# car1r1.net
KiCad netlist of a schematic drawn in EAGLE
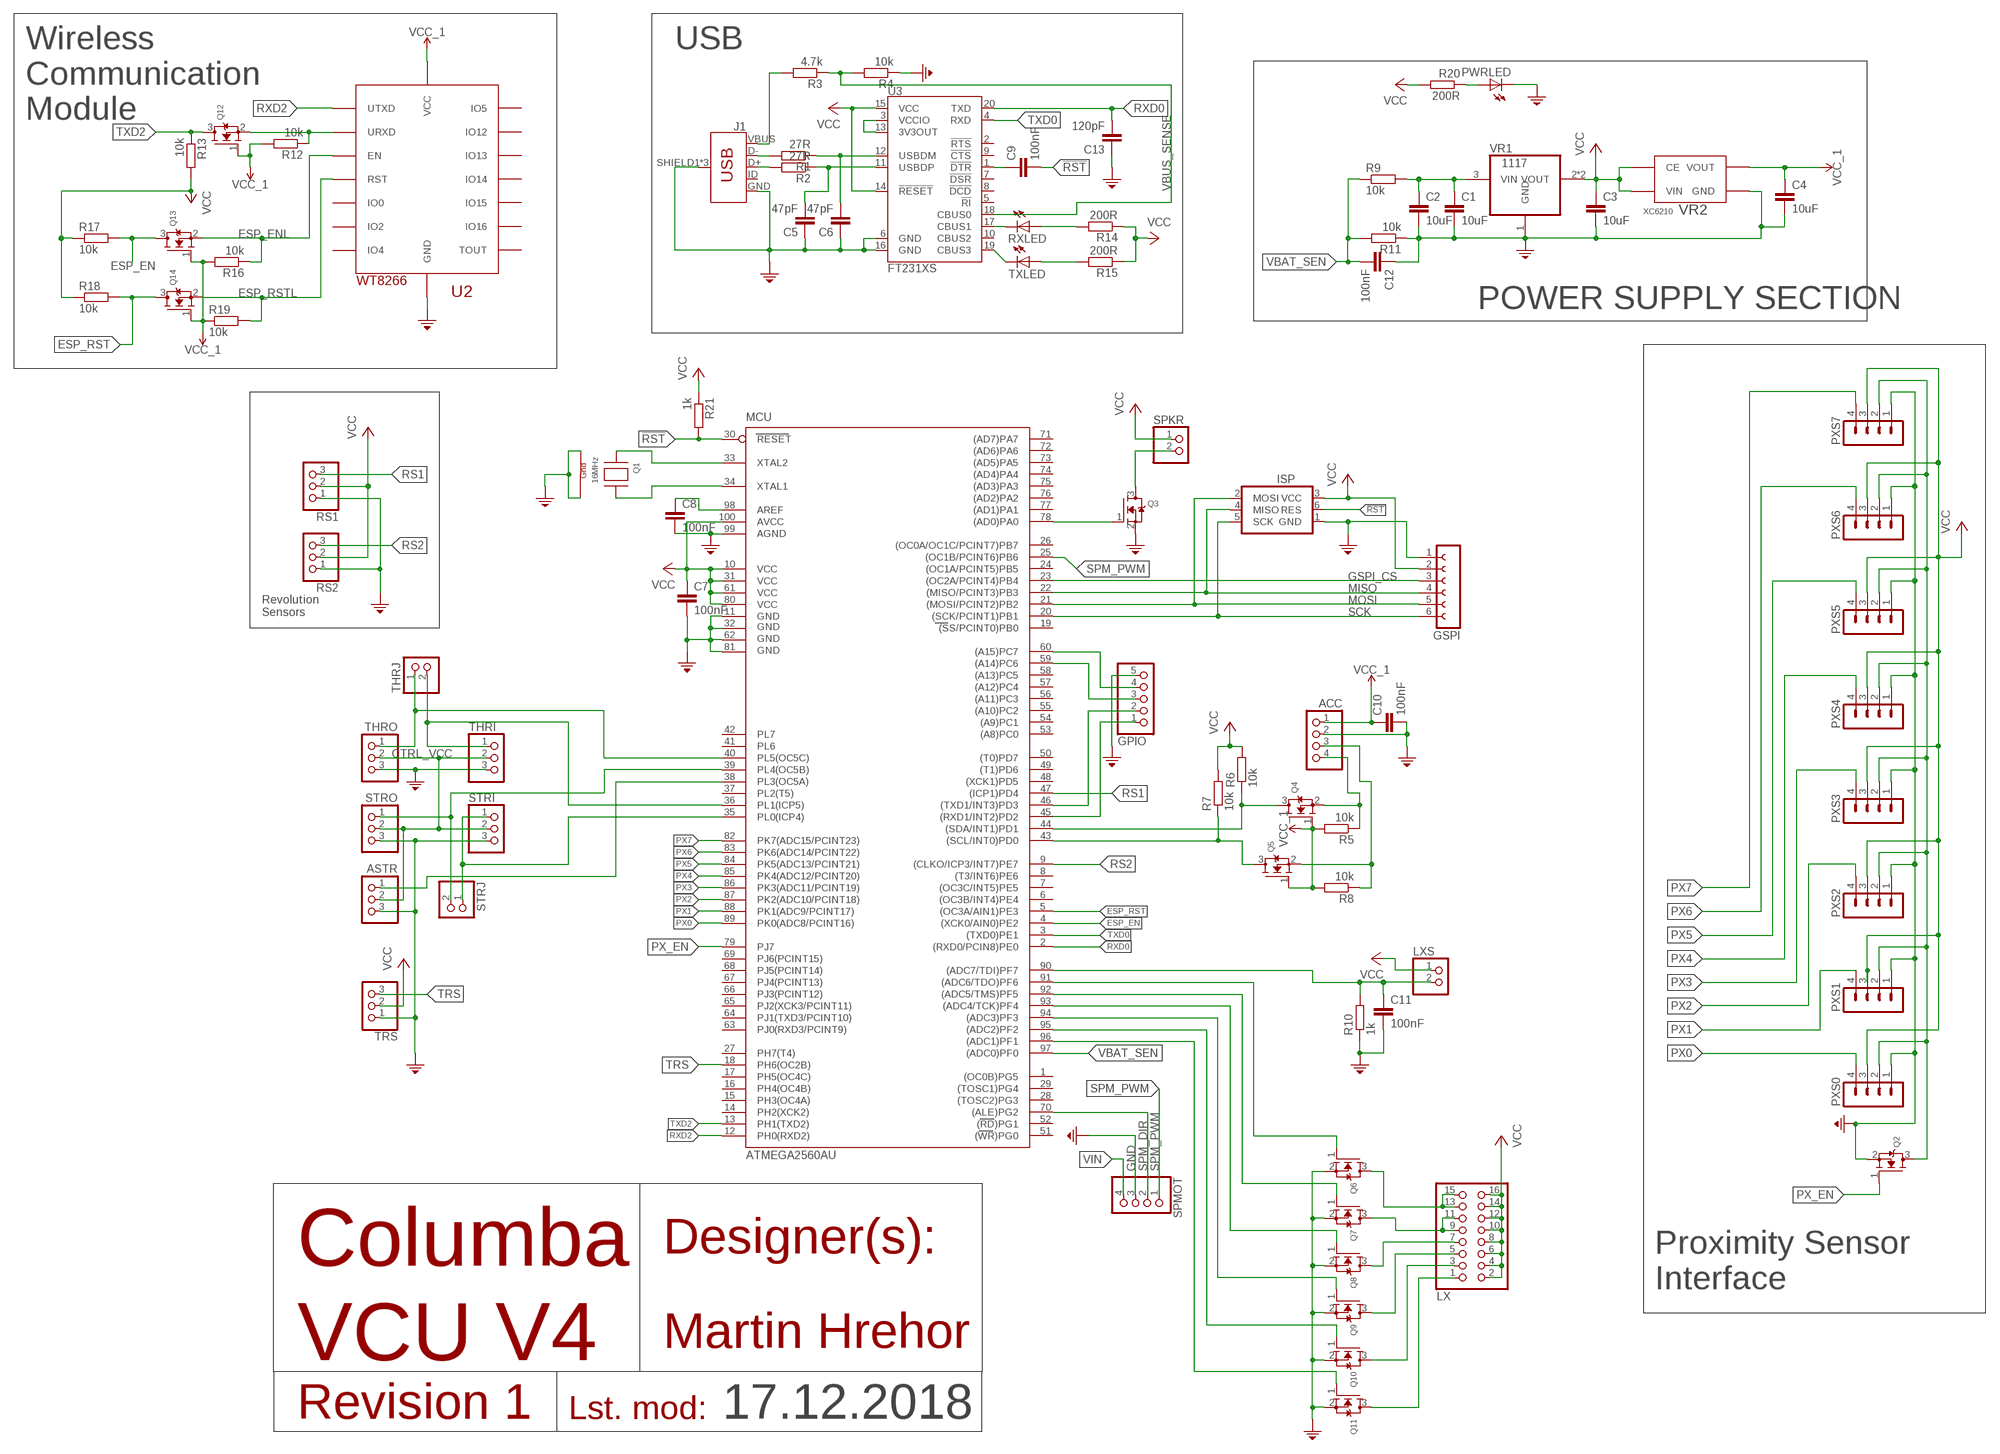
[diagram p0: schematic, sheet 1]

(export (version "E")
  (design (tool "Eeschema 10.0.6"))
  (components
    (comp (ref "ACC")
      (value "PINHD-1X4/90")
      (footprint "eagle-import:1X04_90")
      (libsource (lib "eagle-import") (part "PINHD-1X4/90"))
    )
    (comp (ref "ASTR")
      (value "PINHD-1X3")
      (footprint "eagle-import:1X03")
      (libsource (lib "eagle-import") (part "PINHD-1X3"))
    )
    (comp (ref "C1")
      (value "10uF")
      (footprint "eagle-import:C1206")
      (libsource (lib "eagle-import") (part "C-EUC1206"))
    )
    (comp (ref "C2")
      (value "10uF")
      (footprint "eagle-import:C1206")
      (libsource (lib "eagle-import") (part "C-EUC1206"))
    )
    (comp (ref "C3")
      (value "10uF")
      (footprint "eagle-import:C1206")
      (libsource (lib "eagle-import") (part "C-EUC1206"))
    )
    (comp (ref "C4")
      (value "10uF")
      (footprint "eagle-import:C1206")
      (libsource (lib "eagle-import") (part "C-EUC1206"))
    )
    (comp (ref "C5")
      (value "47pF")
      (footprint "eagle-import:C0603")
      (libsource (lib "eagle-import") (part "C-EUC0603"))
    )
    (comp (ref "C6")
      (value "47pF")
      (footprint "eagle-import:C0603")
      (libsource (lib "eagle-import") (part "C-EUC0603"))
    )
    (comp (ref "C7")
      (value "100nF")
      (footprint "eagle-import:C1206")
      (libsource (lib "eagle-import") (part "C-EUC1206"))
    )
    (comp (ref "C8")
      (value "100nF")
      (footprint "eagle-import:C1206")
      (libsource (lib "eagle-import") (part "C-EUC1206"))
    )
    (comp (ref "C9")
      (value "100nF")
      (footprint "eagle-import:C1206")
      (libsource (lib "eagle-import") (part "C-EUC1206"))
    )
    (comp (ref "C10")
      (value "100nF")
      (footprint "eagle-import:C1206")
      (libsource (lib "eagle-import") (part "C-EUC1206"))
    )
    (comp (ref "C11")
      (value "100nF")
      (footprint "eagle-import:C1206")
      (libsource (lib "eagle-import") (part "C-EUC1206"))
    )
    (comp (ref "C12")
      (value "100nF")
      (footprint "eagle-import:C1206")
      (libsource (lib "eagle-import") (part "C-EUC1206"))
    )
    (comp (ref "C13")
      (value "120pF")
      (footprint "eagle-import:C0603")
      (libsource (lib "eagle-import") (part "C-EUC0603"))
    )
    (comp (ref "GPIO")
      (value "PINHD-1X5")
      (footprint "eagle-import:1X05")
      (libsource (lib "eagle-import") (part "PINHD-1X5"))
    )
    (comp (ref "GSPI")
      (value "FE06W")
      (footprint "eagle-import:FE06W")
      (libsource (lib "eagle-import") (part "FE06W"))
    )
    (comp (ref "ISP")
      (value "ISP")
      (footprint "eagle-import:ISP")
      (libsource (lib "eagle-import") (part "ISP"))
    )
    (comp (ref "J1")
      (value "USB_MICRO-B_FEMALE-SMT")
      (footprint "eagle-import:USB-B-MICRO-SMD")
      (libsource (lib "eagle-import") (part "USB_MICRO-B_FEMALE-SMT"))
    )
    (comp (ref "LX")
      (value "PINHD-2X8")
      (footprint "eagle-import:2X08")
      (libsource (lib "eagle-import") (part "PINHD-2X8"))
    )
    (comp (ref "LXS")
      (value "PINHD-1X2")
      (footprint "eagle-import:1X02")
      (libsource (lib "eagle-import") (part "PINHD-1X2"))
    )
    (comp (ref "MCU")
      (value "ATMEGA2560AU")
      (footprint "eagle-import:TQFP100")
      (libsource (lib "eagle-import") (part "ATMEGA2560AU"))
    )
    (comp (ref "PWRLED")
      (value "LEDCHIP-LED0603")
      (footprint "eagle-import:CHIP-LED0603")
      (libsource (lib "eagle-import") (part "LEDCHIP-LED0603"))
    )
    (comp (ref "PXS0")
      (value "MA04-1")
      (footprint "eagle-import:MA04-1")
      (libsource (lib "eagle-import") (part "MA04-1"))
    )
    (comp (ref "PXS1")
      (value "MA04-1")
      (footprint "eagle-import:MA04-1")
      (libsource (lib "eagle-import") (part "MA04-1"))
    )
    (comp (ref "PXS2")
      (value "MA04-1")
      (footprint "eagle-import:MA04-1")
      (libsource (lib "eagle-import") (part "MA04-1"))
    )
    (comp (ref "PXS3")
      (value "MA04-1")
      (footprint "eagle-import:MA04-1")
      (libsource (lib "eagle-import") (part "MA04-1"))
    )
    (comp (ref "PXS4")
      (value "MA04-1")
      (footprint "eagle-import:MA04-1")
      (libsource (lib "eagle-import") (part "MA04-1"))
    )
    (comp (ref "PXS5")
      (value "MA04-1")
      (footprint "eagle-import:MA04-1")
      (libsource (lib "eagle-import") (part "MA04-1"))
    )
    (comp (ref "PXS6")
      (value "MA04-1")
      (footprint "eagle-import:MA04-1")
      (libsource (lib "eagle-import") (part "MA04-1"))
    )
    (comp (ref "PXS7")
      (value "MA04-1")
      (footprint "eagle-import:MA04-1")
      (libsource (lib "eagle-import") (part "MA04-1"))
    )
    (comp (ref "Q1")
      (value "16MHz")
      (footprint "eagle-import:NX3225")
      (libsource (lib "eagle-import") (part "XTAL-4-3225"))
    )
    (comp (ref "Q2")
      (value "MOSFET-NREFLOW")
      (footprint "eagle-import:SOT23")
      (libsource (lib "eagle-import") (part "MOSFET-NREFLOW"))
    )
    (comp (ref "Q3")
      (value "MOSFET-NREFLOW")
      (footprint "eagle-import:SOT23")
      (libsource (lib "eagle-import") (part "MOSFET-NREFLOW"))
    )
    (comp (ref "Q4")
      (value "MOSFET-NREFLOW")
      (footprint "eagle-import:SOT23")
      (libsource (lib "eagle-import") (part "MOSFET-NREFLOW"))
    )
    (comp (ref "Q5")
      (value "MOSFET-NREFLOW")
      (footprint "eagle-import:SOT23")
      (libsource (lib "eagle-import") (part "MOSFET-NREFLOW"))
    )
    (comp (ref "Q6")
      (value "MOSFET-NREFLOW")
      (footprint "eagle-import:SOT23")
      (libsource (lib "eagle-import") (part "MOSFET-NREFLOW"))
    )
    (comp (ref "Q7")
      (value "MOSFET-NREFLOW")
      (footprint "eagle-import:SOT23")
      (libsource (lib "eagle-import") (part "MOSFET-NREFLOW"))
    )
    (comp (ref "Q8")
      (value "MOSFET-NREFLOW")
      (footprint "eagle-import:SOT23")
      (libsource (lib "eagle-import") (part "MOSFET-NREFLOW"))
    )
    (comp (ref "Q9")
      (value "MOSFET-NREFLOW")
      (footprint "eagle-import:SOT23")
      (libsource (lib "eagle-import") (part "MOSFET-NREFLOW"))
    )
    (comp (ref "Q10")
      (value "MOSFET-NREFLOW")
      (footprint "eagle-import:SOT23")
      (libsource (lib "eagle-import") (part "MOSFET-NREFLOW"))
    )
    (comp (ref "Q11")
      (value "MOSFET-NREFLOW")
      (footprint "eagle-import:SOT23")
      (libsource (lib "eagle-import") (part "MOSFET-NREFLOW"))
    )
    (comp (ref "Q12")
      (value "MOSFET-NREFLOW")
      (footprint "eagle-import:SOT23")
      (libsource (lib "eagle-import") (part "MOSFET-NREFLOW"))
    )
    (comp (ref "Q13")
      (value "MOSFET-NREFLOW")
      (footprint "eagle-import:SOT23")
      (libsource (lib "eagle-import") (part "MOSFET-NREFLOW"))
    )
    (comp (ref "Q14")
      (value "MOSFET-NREFLOW")
      (footprint "eagle-import:SOT23")
      (libsource (lib "eagle-import") (part "MOSFET-NREFLOW"))
    )
    (comp (ref "R1")
      (value "27R")
      (footprint "eagle-import:R0603")
      (libsource (lib "eagle-import") (part "R-EU_R0603"))
    )
    (comp (ref "R2")
      (value "27R")
      (footprint "eagle-import:R0603")
      (libsource (lib "eagle-import") (part "R-EU_R0603"))
    )
    (comp (ref "R3")
      (value "4.7k")
      (footprint "eagle-import:R0603")
      (libsource (lib "eagle-import") (part "R-EU_R0603"))
    )
    (comp (ref "R4")
      (value "10k")
      (footprint "eagle-import:R0603")
      (libsource (lib "eagle-import") (part "R-EU_R0603"))
    )
    (comp (ref "R5")
      (value "10k")
      (footprint "eagle-import:R0603")
      (libsource (lib "eagle-import") (part "R-EU_R0603"))
    )
    (comp (ref "R6")
      (value "10k")
      (footprint "eagle-import:R0603")
      (libsource (lib "eagle-import") (part "R-EU_R0603"))
    )
    (comp (ref "R7")
      (value "10k")
      (footprint "eagle-import:R0603")
      (libsource (lib "eagle-import") (part "R-EU_R0603"))
    )
    (comp (ref "R8")
      (value "10k")
      (footprint "eagle-import:R0603")
      (libsource (lib "eagle-import") (part "R-EU_R0603"))
    )
    (comp (ref "R9")
      (value "10k")
      (footprint "eagle-import:R0805")
      (libsource (lib "eagle-import") (part "R-EU_R0805"))
    )
    (comp (ref "R10")
      (value "1k")
      (footprint "eagle-import:R0603")
      (libsource (lib "eagle-import") (part "R-EU_R0603"))
    )
    (comp (ref "R11")
      (value "10k")
      (footprint "eagle-import:R0805")
      (libsource (lib "eagle-import") (part "R-EU_R0805"))
    )
    (comp (ref "R12")
      (value "10k")
      (footprint "eagle-import:R0603")
      (libsource (lib "eagle-import") (part "R-EU_R0603"))
    )
    (comp (ref "R13")
      (value "10k")
      (footprint "eagle-import:R0603")
      (libsource (lib "eagle-import") (part "R-EU_R0603"))
    )
    (comp (ref "R14")
      (value "200R")
      (footprint "eagle-import:R0603")
      (libsource (lib "eagle-import") (part "R-EU_R0603"))
    )
    (comp (ref "R15")
      (value "200R")
      (footprint "eagle-import:R0603")
      (libsource (lib "eagle-import") (part "R-EU_R0603"))
    )
    (comp (ref "R16")
      (value "10k")
      (footprint "eagle-import:R0603")
      (libsource (lib "eagle-import") (part "R-EU_R0603"))
    )
    (comp (ref "R17")
      (value "10k")
      (footprint "eagle-import:R0603")
      (libsource (lib "eagle-import") (part "R-EU_R0603"))
    )
    (comp (ref "R18")
      (value "10k")
      (footprint "eagle-import:R0603")
      (libsource (lib "eagle-import") (part "R-EU_R0603"))
    )
    (comp (ref "R19")
      (value "10k")
      (footprint "eagle-import:R0603")
      (libsource (lib "eagle-import") (part "R-EU_R0603"))
    )
    (comp (ref "R20")
      (value "200R")
      (footprint "eagle-import:R0603")
      (libsource (lib "eagle-import") (part "R-EU_R0603"))
    )
    (comp (ref "R21")
      (value "1k")
      (footprint "eagle-import:R0603")
      (libsource (lib "eagle-import") (part "R-EU_R0603"))
    )
    (comp (ref "RS1")
      (value "PINHD-1X3")
      (footprint "eagle-import:1X03")
      (libsource (lib "eagle-import") (part "PINHD-1X3"))
    )
    (comp (ref "RS2")
      (value "PINHD-1X3")
      (footprint "eagle-import:1X03")
      (libsource (lib "eagle-import") (part "PINHD-1X3"))
    )
    (comp (ref "RXLED")
      (value "LEDCHIP-LED0603")
      (footprint "eagle-import:CHIP-LED0603")
      (libsource (lib "eagle-import") (part "LEDCHIP-LED0603"))
    )
    (comp (ref "SPKR")
      (value "PINHD-1X2")
      (footprint "eagle-import:1X02")
      (libsource (lib "eagle-import") (part "PINHD-1X2"))
    )
    (comp (ref "SPMOT")
      (value "PINHD-1X4/90")
      (footprint "eagle-import:1X04_90")
      (libsource (lib "eagle-import") (part "PINHD-1X4/90"))
    )
    (comp (ref "STRI")
      (value "PINHD-1X3")
      (footprint "eagle-import:1X03")
      (libsource (lib "eagle-import") (part "PINHD-1X3"))
    )
    (comp (ref "STRJ")
      (value "PINHD-1X2")
      (footprint "eagle-import:1X02")
      (libsource (lib "eagle-import") (part "PINHD-1X2"))
    )
    (comp (ref "STRO")
      (value "PINHD-1X3")
      (footprint "eagle-import:1X03")
      (libsource (lib "eagle-import") (part "PINHD-1X3"))
    )
    (comp (ref "THRI")
      (value "PINHD-1X3")
      (footprint "eagle-import:1X03")
      (libsource (lib "eagle-import") (part "PINHD-1X3"))
    )
    (comp (ref "THRJ")
      (value "PINHD-1X2")
      (footprint "eagle-import:1X02")
      (libsource (lib "eagle-import") (part "PINHD-1X2"))
    )
    (comp (ref "THRO")
      (value "PINHD-1X3")
      (footprint "eagle-import:1X03")
      (libsource (lib "eagle-import") (part "PINHD-1X3"))
    )
    (comp (ref "TRS")
      (value "PINHD-1X3")
      (footprint "eagle-import:1X03")
      (libsource (lib "eagle-import") (part "PINHD-1X3"))
    )
    (comp (ref "TXLED")
      (value "LEDCHIP-LED0603")
      (footprint "eagle-import:CHIP-LED0603")
      (libsource (lib "eagle-import") (part "LEDCHIP-LED0603"))
    )
    (comp (ref "U2")
      (value "WT8266")
      (footprint "eagle-import:WT8266")
      (libsource (lib "eagle-import") (part "WT8266"))
    )
    (comp (ref "U3")
      (value "FT231XS")
      (footprint "eagle-import:SSOP20_L")
      (libsource (lib "eagle-import") (part "FT231XS"))
    )
    (comp (ref "VR1")
      (value "1117")
      (footprint "eagle-import:SOT223")
      (fields (field (name "MPN") "REG1117"))
      (libsource (lib "eagle-import") (part "REG1117"))
    )
    (comp (ref "VR2")
      (value "XC6210")
      (footprint "eagle-import:SOT25")
      (libsource (lib "eagle-import") (part "XC6210"))
    )
  )
  (nets
    (net (code "1") (name "/CTRL_VCC") (class "Default")
      (node (ref "ASTR") (pin "2") (pinfunction "2_2") (pintype "passive"))
      (node (ref "STRI") (pin "2") (pinfunction "2_2") (pintype "passive"))
      (node (ref "STRO") (pin "2") (pinfunction "2_2") (pintype "passive"))
      (node (ref "THRI") (pin "2") (pinfunction "2_2") (pintype "passive"))
      (node (ref "THRO") (pin "2") (pinfunction "2_2") (pintype "passive"))
    )
    (net (code "2") (name "/ESP_ENL") (class "Default")
      (node (ref "Q13") (pin "2") (pinfunction "S_2") (pintype "bidirectional"))
      (node (ref "R16") (pin "1") (pinfunction "1_1") (pintype "passive"))
      (node (ref "U2") (pin "EN") (pinfunction "EN_EN") (pintype "bidirectional"))
    )
    (net (code "3") (name "/ESP_RSTL") (class "Default")
      (node (ref "Q14") (pin "2") (pinfunction "S_2") (pintype "bidirectional"))
      (node (ref "R19") (pin "2") (pinfunction "2_2") (pintype "passive"))
      (node (ref "U2") (pin "RST") (pinfunction "RST_RST") (pintype "bidirectional"))
    )
    (net (code "4") (name "/GSPI_CS") (class "Default")
      (node (ref "GSPI") (pin "3") (pinfunction "3_3") (pintype "passive"))
      (node (ref "MCU") (pin "23") (pinfunction "(OC2A/PCINT4)PB4_23") (pintype "bidirectional"))
    )
    (net (code "5") (name "/MISO") (class "Default")
      (node (ref "GSPI") (pin "4") (pinfunction "4_4") (pintype "passive"))
      (node (ref "ISP") (pin "4") (pinfunction "MISO_4") (pintype "bidirectional"))
      (node (ref "MCU") (pin "22") (pinfunction "(MISO/PCINT3)PB3_22") (pintype "bidirectional"))
    )
    (net (code "6") (name "/MOSI") (class "Default")
      (node (ref "GSPI") (pin "5") (pinfunction "5_5") (pintype "passive"))
      (node (ref "ISP") (pin "2") (pinfunction "MOSI_2") (pintype "bidirectional"))
      (node (ref "MCU") (pin "21") (pinfunction "(MOSI/PCINT2)PB2_21") (pintype "bidirectional"))
    )
    (net (code "7") (name "/SCK") (class "Default")
      (node (ref "GSPI") (pin "6") (pinfunction "6_6") (pintype "passive"))
      (node (ref "ISP") (pin "5") (pinfunction "SCK_5") (pintype "bidirectional"))
      (node (ref "MCU") (pin "20") (pinfunction "(SCK/PCINT1)PB1_20") (pintype "bidirectional"))
    )
    (net (code "8") (name "/SPM_DIR") (class "Default")
      (node (ref "MCU") (pin "70") (pinfunction "(ALE)PG2_70") (pintype "bidirectional"))
      (node (ref "SPMOT") (pin "2") (pinfunction "2_2") (pintype "passive"))
    )
    (net (code "9") (name "/VBUS_SENSE") (class "Default")
      (node (ref "R3") (pin "1") (pinfunction "1_1") (pintype "passive"))
      (node (ref "R4") (pin "2") (pinfunction "2_2") (pintype "passive"))
      (node (ref "U3") (pin "18") (pinfunction "CBUS0_18") (pintype "bidirectional"))
    )
    (net (code "10") (name "/~{RST}") (class "Default")
      (node (ref "C9") (pin "2") (pinfunction "2_2") (pintype "passive"))
      (node (ref "ISP") (pin "6") (pinfunction "RES_6") (pintype "bidirectional"))
      (node (ref "MCU") (pin "30") (pinfunction "RESET_30") (pintype "input"))
      (node (ref "R21") (pin "2") (pinfunction "2_2") (pintype "passive"))
    )
    (net (code "11") (name "ESP_EN") (class "Default")
      (node (ref "MCU") (pin "4") (pinfunction "(XCK0/AIN0)PE2_4") (pintype "bidirectional"))
      (node (ref "Q13") (pin "3") (pinfunction "D_3") (pintype "bidirectional"))
      (node (ref "R17") (pin "2") (pinfunction "2_2") (pintype "passive"))
    )
    (net (code "12") (name "ESP_RST") (class "Default")
      (node (ref "MCU") (pin "5") (pinfunction "(OC3A/AIN1)PE3_5") (pintype "bidirectional"))
      (node (ref "Q14") (pin "3") (pinfunction "D_3") (pintype "bidirectional"))
      (node (ref "R18") (pin "2") (pinfunction "2_2") (pintype "passive"))
    )
    (net (code "13") (name "GND") (class "Default")
      (node (ref "ACC") (pin "2") (pinfunction "2_2") (pintype "passive"))
      (node (ref "ASTR") (pin "3") (pinfunction "3_3") (pintype "passive"))
      (node (ref "C1") (pin "2") (pinfunction "2_2") (pintype "passive"))
      (node (ref "C10") (pin "2") (pinfunction "2_2") (pintype "passive"))
      (node (ref "C11") (pin "2") (pinfunction "2_2") (pintype "passive"))
      (node (ref "C12") (pin "1") (pinfunction "1_1") (pintype "passive"))
      (node (ref "C13") (pin "1") (pinfunction "1_1") (pintype "passive"))
      (node (ref "C2") (pin "2") (pinfunction "2_2") (pintype "passive"))
      (node (ref "C3") (pin "2") (pinfunction "2_2") (pintype "passive"))
      (node (ref "C4") (pin "2") (pinfunction "2_2") (pintype "passive"))
      (node (ref "C5") (pin "1") (pinfunction "1_1") (pintype "passive"))
      (node (ref "C6") (pin "1") (pinfunction "1_1") (pintype "passive"))
      (node (ref "C7") (pin "2") (pinfunction "2_2") (pintype "passive"))
      (node (ref "C8") (pin "2") (pinfunction "2_2") (pintype "passive"))
      (node (ref "GPIO") (pin "5") (pinfunction "5_5") (pintype "passive"))
      (node (ref "GSPI") (pin "1") (pinfunction "1_1") (pintype "passive"))
      (node (ref "ISP") (pin "1") (pinfunction "GND_1") (pintype "bidirectional"))
      (node (ref "J1") (pin "GND") (pinfunction "GND_GND") (pintype "power_in"))
      (node (ref "J1") (pin "SHIELD1") (pinfunction "SHIELD_SHIELD1") (pintype "bidirectional"))
      (node (ref "J1") (pin "SHIELD2") (pinfunction "SHIELD_SHIELD2") (pintype "bidirectional"))
      (node (ref "J1") (pin "SHIELD3") (pinfunction "SHIELD_SHIELD3") (pintype "bidirectional"))
      (node (ref "MCU") (pin "11") (pinfunction "GND_11") (pintype "power_in"))
      (node (ref "MCU") (pin "32") (pinfunction "GND1_32") (pintype "power_in"))
      (node (ref "MCU") (pin "62") (pinfunction "GND2_62") (pintype "power_in"))
      (node (ref "MCU") (pin "81") (pinfunction "GND3_81") (pintype "power_in"))
      (node (ref "MCU") (pin "99") (pinfunction "AGND_99") (pintype "power_in"))
      (node (ref "PWRLED") (pin "C") (pinfunction "C_C") (pintype "passive"))
      (node (ref "PXS0") (pin "1") (pinfunction "1_1") (pintype "passive"))
      (node (ref "PXS1") (pin "1") (pinfunction "1_1") (pintype "passive"))
      (node (ref "PXS2") (pin "1") (pinfunction "1_1") (pintype "passive"))
      (node (ref "PXS3") (pin "1") (pinfunction "1_1") (pintype "passive"))
      (node (ref "PXS4") (pin "1") (pinfunction "1_1") (pintype "passive"))
      (node (ref "PXS5") (pin "1") (pinfunction "1_1") (pintype "passive"))
      (node (ref "PXS6") (pin "1") (pinfunction "1_1") (pintype "passive"))
      (node (ref "PXS7") (pin "1") (pinfunction "1_1") (pintype "passive"))
      (node (ref "Q1") (pin "2") (pinfunction "G2_2") (pintype "power_in"))
      (node (ref "Q1") (pin "4") (pinfunction "G1_4") (pintype "power_in"))
      (node (ref "Q10") (pin "2") (pinfunction "S_2") (pintype "bidirectional"))
      (node (ref "Q11") (pin "2") (pinfunction "S_2") (pintype "bidirectional"))
      (node (ref "Q2") (pin "2") (pinfunction "S_2") (pintype "bidirectional"))
      (node (ref "Q3") (pin "2") (pinfunction "S_2") (pintype "bidirectional"))
      (node (ref "Q6") (pin "2") (pinfunction "S_2") (pintype "bidirectional"))
      (node (ref "Q7") (pin "2") (pinfunction "S_2") (pintype "bidirectional"))
      (node (ref "Q8") (pin "2") (pinfunction "S_2") (pintype "bidirectional"))
      (node (ref "Q9") (pin "2") (pinfunction "S_2") (pintype "bidirectional"))
      (node (ref "R10") (pin "1") (pinfunction "1_1") (pintype "passive"))
      (node (ref "R11") (pin "1") (pinfunction "1_1") (pintype "passive"))
      (node (ref "R4") (pin "1") (pinfunction "1_1") (pintype "passive"))
      (node (ref "RS1") (pin "1") (pinfunction "1_1") (pintype "passive"))
      (node (ref "RS2") (pin "1") (pinfunction "1_1") (pintype "passive"))
      (node (ref "SPMOT") (pin "3") (pinfunction "3_3") (pintype "passive"))
      (node (ref "STRI") (pin "3") (pinfunction "3_3") (pintype "passive"))
      (node (ref "STRO") (pin "3") (pinfunction "3_3") (pintype "passive"))
      (node (ref "THRI") (pin "3") (pinfunction "3_3") (pintype "passive"))
      (node (ref "THRO") (pin "3") (pinfunction "3_3") (pintype "passive"))
      (node (ref "TRS") (pin "1") (pinfunction "1_1") (pintype "passive"))
      (node (ref "U2") (pin "GND0") (pinfunction "GND_GND0") (pintype "power_in"))
      (node (ref "U2") (pin "GND1") (pinfunction "GND_GND1") (pintype "power_in"))
      (node (ref "U2") (pin "GND2") (pinfunction "GND_GND2") (pintype "power_in"))
      (node (ref "U3") (pin "16") (pinfunction "GND_16") (pintype "bidirectional"))
      (node (ref "U3") (pin "6") (pinfunction "GND_6") (pintype "bidirectional"))
      (node (ref "VR1") (pin "1") (pinfunction "GND_1") (pintype "power_in"))
      (node (ref "VR2") (pin "2") (pinfunction "GND_2") (pintype "power_in"))
    )
    (net (code "14") (name "Net-(J1-PadD+)") (class "Default")
      (node (ref "J1") (pin "D+") (pinfunction "D+_D+") (pintype "bidirectional"))
      (node (ref "R2") (pin "2") (pinfunction "2_2") (pintype "passive"))
    )
    (net (code "15") (name "Net-(J1-PadD-)") (class "Default")
      (node (ref "J1") (pin "D-") (pinfunction "D-_D-") (pintype "bidirectional"))
      (node (ref "R1") (pin "2") (pinfunction "2_2") (pintype "passive"))
    )
    (net (code "16") (name "Net-(J1-PadVBUS)") (class "Default")
      (node (ref "J1") (pin "VBUS") (pinfunction "VBUS_VBUS") (pintype "power_in"))
      (node (ref "R3") (pin "2") (pinfunction "2_2") (pintype "passive"))
    )
    (net (code "17") (name "Net-(MCU-(A14)PC6)") (class "Default")
      (node (ref "GPIO") (pin "3") (pinfunction "3_3") (pintype "passive"))
      (node (ref "MCU") (pin "59") (pinfunction "(A14)PC6_59") (pintype "bidirectional"))
    )
    (net (code "18") (name "Net-(MCU-(A15)PC7)") (class "Default")
      (node (ref "GPIO") (pin "4") (pinfunction "4_4") (pintype "passive"))
      (node (ref "MCU") (pin "60") (pinfunction "(A15)PC7_60") (pintype "bidirectional"))
    )
    (net (code "19") (name "Net-(MCU-(AD0)PA0)") (class "Default")
      (node (ref "MCU") (pin "78") (pinfunction "(AD0)PA0_78") (pintype "bidirectional"))
      (node (ref "Q3") (pin "1") (pinfunction "G_1") (pintype "bidirectional"))
    )
    (net (code "20") (name "Net-(MCU-(ADC1)PF1)") (class "Default")
      (node (ref "MCU") (pin "96") (pinfunction "(ADC1)PF1_96") (pintype "bidirectional"))
      (node (ref "Q11") (pin "1") (pinfunction "G_1") (pintype "bidirectional"))
    )
    (net (code "21") (name "Net-(MCU-(ADC2)PF2)") (class "Default")
      (node (ref "MCU") (pin "95") (pinfunction "(ADC2)PF2_95") (pintype "bidirectional"))
      (node (ref "Q10") (pin "1") (pinfunction "G_1") (pintype "bidirectional"))
    )
    (net (code "22") (name "Net-(MCU-(ADC3)PF3)") (class "Default")
      (node (ref "MCU") (pin "94") (pinfunction "(ADC3)PF3_94") (pintype "bidirectional"))
      (node (ref "Q9") (pin "1") (pinfunction "G_1") (pintype "bidirectional"))
    )
    (net (code "23") (name "Net-(MCU-(ADC4{slash}TCK)PF4)") (class "Default")
      (node (ref "MCU") (pin "93") (pinfunction "(ADC4/TCK)PF4_93") (pintype "bidirectional"))
      (node (ref "Q8") (pin "1") (pinfunction "G_1") (pintype "bidirectional"))
    )
    (net (code "24") (name "Net-(MCU-(ADC5{slash}TMS)PF5)") (class "Default")
      (node (ref "MCU") (pin "92") (pinfunction "(ADC5/TMS)PF5_92") (pintype "bidirectional"))
      (node (ref "Q7") (pin "1") (pinfunction "G_1") (pintype "bidirectional"))
    )
    (net (code "25") (name "Net-(MCU-(ADC6{slash}TDO)PF6)") (class "Default")
      (node (ref "MCU") (pin "91") (pinfunction "(ADC6/TDO)PF6_91") (pintype "bidirectional"))
      (node (ref "Q6") (pin "1") (pinfunction "G_1") (pintype "bidirectional"))
    )
    (net (code "26") (name "Net-(MCU-(ADC7{slash}TDI)PF7)") (class "Default")
      (node (ref "C11") (pin "1") (pinfunction "1_1") (pintype "passive"))
      (node (ref "LXS") (pin "2") (pinfunction "2_2") (pintype "passive"))
      (node (ref "MCU") (pin "90") (pinfunction "(ADC7/TDI)PF7_90") (pintype "bidirectional"))
      (node (ref "R10") (pin "2") (pinfunction "2_2") (pintype "passive"))
    )
    (net (code "27") (name "Net-(MCU-(RXD1{slash}INT2)PD2)") (class "Default")
      (node (ref "GPIO") (pin "1") (pinfunction "1_1") (pintype "passive"))
      (node (ref "MCU") (pin "45") (pinfunction "(RXD1/INT2)PD2_45") (pintype "bidirectional"))
    )
    (net (code "28") (name "Net-(MCU-(SCL{slash}INT0)PD0)") (class "Default")
      (node (ref "MCU") (pin "43") (pinfunction "(SCL/INT0)PD0_43") (pintype "bidirectional"))
      (node (ref "Q5") (pin "3") (pinfunction "D_3") (pintype "bidirectional"))
      (node (ref "R7") (pin "1") (pinfunction "1_1") (pintype "passive"))
    )
    (net (code "29") (name "Net-(MCU-(SDA{slash}INT1)PD1)") (class "Default")
      (node (ref "MCU") (pin "44") (pinfunction "(SDA/INT1)PD1_44") (pintype "bidirectional"))
      (node (ref "Q4") (pin "3") (pinfunction "D_3") (pintype "bidirectional"))
      (node (ref "R6") (pin "1") (pinfunction "1_1") (pintype "passive"))
    )
    (net (code "30") (name "Net-(MCU-(TXD1{slash}INT3)PD3)") (class "Default")
      (node (ref "GPIO") (pin "2") (pinfunction "2_2") (pintype "passive"))
      (node (ref "MCU") (pin "46") (pinfunction "(TXD1/INT3)PD3_46") (pintype "bidirectional"))
    )
    (net (code "31") (name "Net-(MCU-AREF)") (class "Default")
      (node (ref "C8") (pin "1") (pinfunction "1_1") (pintype "passive"))
      (node (ref "MCU") (pin "98") (pinfunction "AREF_98") (pintype "bidirectional"))
    )
    (net (code "32") (name "Net-(MCU-PL0(ICP4))") (class "Default")
      (node (ref "MCU") (pin "35") (pinfunction "PL0(ICP4)_35") (pintype "bidirectional"))
      (node (ref "STRI") (pin "1") (pinfunction "1_1") (pintype "passive"))
      (node (ref "STRJ") (pin "1") (pinfunction "1_1") (pintype "passive"))
    )
    (net (code "33") (name "Net-(MCU-PL1(ICP5))") (class "Default")
      (node (ref "MCU") (pin "36") (pinfunction "PL1(ICP5)_36") (pintype "bidirectional"))
      (node (ref "THRI") (pin "1") (pinfunction "1_1") (pintype "passive"))
      (node (ref "THRJ") (pin "2") (pinfunction "2_2") (pintype "passive"))
    )
    (net (code "34") (name "Net-(MCU-PL3(OC5A))") (class "Default")
      (node (ref "ASTR") (pin "1") (pinfunction "1_1") (pintype "passive"))
      (node (ref "MCU") (pin "38") (pinfunction "PL3(OC5A)_38") (pintype "bidirectional"))
    )
    (net (code "35") (name "Net-(MCU-PL4(OC5B))") (class "Default")
      (node (ref "MCU") (pin "39") (pinfunction "PL4(OC5B)_39") (pintype "bidirectional"))
      (node (ref "STRJ") (pin "2") (pinfunction "2_2") (pintype "passive"))
      (node (ref "STRO") (pin "1") (pinfunction "1_1") (pintype "passive"))
    )
    (net (code "36") (name "Net-(MCU-PL5(OC5C))") (class "Default")
      (node (ref "MCU") (pin "40") (pinfunction "PL5(OC5C)_40") (pintype "bidirectional"))
      (node (ref "THRJ") (pin "1") (pinfunction "1_1") (pintype "passive"))
      (node (ref "THRO") (pin "1") (pinfunction "1_1") (pintype "passive"))
    )
    (net (code "37") (name "Net-(MCU-XTAL1)") (class "Default")
      (node (ref "MCU") (pin "34") (pinfunction "XTAL1_34") (pintype "input"))
      (node (ref "Q1") (pin "3") (pinfunction "X2_3") (pintype "bidirectional"))
    )
    (net (code "38") (name "Net-(MCU-XTAL2)") (class "Default")
      (node (ref "MCU") (pin "33") (pinfunction "XTAL2_33") (pintype "output"))
      (node (ref "Q1") (pin "1") (pinfunction "X1_1") (pintype "bidirectional"))
    )
    (net (code "39") (name "Net-(PWRLED-PadA)") (class "Default")
      (node (ref "PWRLED") (pin "A") (pinfunction "A_A") (pintype "passive"))
      (node (ref "R20") (pin "1") (pinfunction "1_1") (pintype "passive"))
    )
    (net (code "40") (name "Net-(Q2-D)") (class "Default")
      (node (ref "PXS0") (pin "2") (pinfunction "2_2") (pintype "passive"))
      (node (ref "PXS1") (pin "2") (pinfunction "2_2") (pintype "passive"))
      (node (ref "PXS2") (pin "2") (pinfunction "2_2") (pintype "passive"))
      (node (ref "PXS3") (pin "2") (pinfunction "2_2") (pintype "passive"))
      (node (ref "PXS4") (pin "2") (pinfunction "2_2") (pintype "passive"))
      (node (ref "PXS5") (pin "2") (pinfunction "2_2") (pintype "passive"))
      (node (ref "PXS6") (pin "2") (pinfunction "2_2") (pintype "passive"))
      (node (ref "PXS7") (pin "2") (pinfunction "2_2") (pintype "passive"))
      (node (ref "Q2") (pin "3") (pinfunction "D_3") (pintype "bidirectional"))
    )
    (net (code "41") (name "Net-(Q3-D)") (class "Default")
      (node (ref "Q3") (pin "3") (pinfunction "D_3") (pintype "bidirectional"))
      (node (ref "SPKR") (pin "2") (pinfunction "2_2") (pintype "passive"))
    )
    (net (code "42") (name "Net-(Q4-S)") (class "Default")
      (node (ref "ACC") (pin "4") (pinfunction "4_4") (pintype "passive"))
      (node (ref "Q4") (pin "2") (pinfunction "S_2") (pintype "bidirectional"))
      (node (ref "R5") (pin "1") (pinfunction "1_1") (pintype "passive"))
    )
    (net (code "43") (name "Net-(Q5-S)") (class "Default")
      (node (ref "ACC") (pin "3") (pinfunction "3_3") (pintype "passive"))
      (node (ref "Q5") (pin "2") (pinfunction "S_2") (pintype "bidirectional"))
      (node (ref "R8") (pin "1") (pinfunction "1_1") (pintype "passive"))
    )
    (net (code "44") (name "Net-(Q6-D)") (class "Default")
      (node (ref "LX") (pin "13") (pinfunction "13_13") (pintype "passive"))
      (node (ref "LX") (pin "15") (pinfunction "15_15") (pintype "passive"))
      (node (ref "Q6") (pin "3") (pinfunction "D_3") (pintype "bidirectional"))
    )
    (net (code "45") (name "Net-(Q7-D)") (class "Default")
      (node (ref "LX") (pin "11") (pinfunction "11_11") (pintype "passive"))
      (node (ref "LX") (pin "9") (pinfunction "9_9") (pintype "passive"))
      (node (ref "Q7") (pin "3") (pinfunction "D_3") (pintype "bidirectional"))
    )
    (net (code "46") (name "Net-(Q8-D)") (class "Default")
      (node (ref "LX") (pin "7") (pinfunction "7_7") (pintype "passive"))
      (node (ref "Q8") (pin "3") (pinfunction "D_3") (pintype "bidirectional"))
    )
    (net (code "47") (name "Net-(Q9-D)") (class "Default")
      (node (ref "LX") (pin "5") (pinfunction "5_5") (pintype "passive"))
      (node (ref "Q9") (pin "3") (pinfunction "D_3") (pintype "bidirectional"))
    )
    (net (code "48") (name "Net-(Q10-D)") (class "Default")
      (node (ref "LX") (pin "3") (pinfunction "3_3") (pintype "passive"))
      (node (ref "Q10") (pin "3") (pinfunction "D_3") (pintype "bidirectional"))
    )
    (net (code "49") (name "Net-(Q11-D)") (class "Default")
      (node (ref "LX") (pin "1") (pinfunction "1_1") (pintype "passive"))
      (node (ref "Q11") (pin "3") (pinfunction "D_3") (pintype "bidirectional"))
    )
    (net (code "50") (name "Net-(Q12-S)") (class "Default")
      (node (ref "Q12") (pin "2") (pinfunction "S_2") (pintype "bidirectional"))
      (node (ref "R12") (pin "1") (pinfunction "1_1") (pintype "passive"))
      (node (ref "U2") (pin "URXD") (pinfunction "URXD_URXD") (pintype "bidirectional"))
    )
    (net (code "51") (name "Net-(R14-Pad2)") (class "Default")
      (node (ref "R14") (pin "2") (pinfunction "2_2") (pintype "passive"))
      (node (ref "RXLED") (pin "A") (pinfunction "A_A") (pintype "passive"))
    )
    (net (code "52") (name "Net-(R15-Pad2)") (class "Default")
      (node (ref "R15") (pin "2") (pinfunction "2_2") (pintype "passive"))
      (node (ref "TXLED") (pin "A") (pinfunction "A_A") (pintype "passive"))
    )
    (net (code "53") (name "Net-(U3-3V3OUT)") (class "Default")
      (node (ref "U3") (pin "13") (pinfunction "3V3OUT_13") (pintype "bidirectional"))
      (node (ref "U3") (pin "3") (pinfunction "VCCIO_3") (pintype "bidirectional"))
    )
    (net (code "54") (name "Net-(U3-CBUS1)") (class "Default")
      (node (ref "RXLED") (pin "C") (pinfunction "C_C") (pintype "passive"))
      (node (ref "U3") (pin "17") (pinfunction "CBUS1_17") (pintype "bidirectional"))
    )
    (net (code "55") (name "Net-(U3-CBUS3)") (class "Default")
      (node (ref "TXLED") (pin "C") (pinfunction "C_C") (pintype "passive"))
      (node (ref "U3") (pin "19") (pinfunction "CBUS3_19") (pintype "bidirectional"))
    )
    (net (code "56") (name "Net-(U3-USBDM)") (class "Default")
      (node (ref "C6") (pin "2") (pinfunction "2_2") (pintype "passive"))
      (node (ref "R1") (pin "1") (pinfunction "1_1") (pintype "passive"))
      (node (ref "U3") (pin "12") (pinfunction "USBDM_12") (pintype "bidirectional"))
    )
    (net (code "57") (name "Net-(U3-USBDP)") (class "Default")
      (node (ref "C5") (pin "2") (pinfunction "2_2") (pintype "passive"))
      (node (ref "R2") (pin "1") (pinfunction "1_1") (pintype "passive"))
      (node (ref "U3") (pin "11") (pinfunction "USBDP_11") (pintype "bidirectional"))
    )
    (net (code "58") (name "Net-(U3-~{DTR})") (class "Default")
      (node (ref "C9") (pin "1") (pinfunction "1_1") (pintype "passive"))
      (node (ref "U3") (pin "1") (pinfunction "~{DTR}_1") (pintype "bidirectional"))
    )
    (net (code "59") (name "PX0") (class "Default")
      (node (ref "MCU") (pin "89") (pinfunction "PK0(ADC8/PCINT16)_89") (pintype "bidirectional"))
      (node (ref "PXS0") (pin "4") (pinfunction "4_4") (pintype "passive"))
    )
    (net (code "60") (name "PX1") (class "Default")
      (node (ref "MCU") (pin "88") (pinfunction "PK1(ADC9/PCINT17)_88") (pintype "bidirectional"))
      (node (ref "PXS1") (pin "4") (pinfunction "4_4") (pintype "passive"))
    )
    (net (code "61") (name "PX2") (class "Default")
      (node (ref "MCU") (pin "87") (pinfunction "PK2(ADC10/PCINT18)_87") (pintype "bidirectional"))
      (node (ref "PXS2") (pin "4") (pinfunction "4_4") (pintype "passive"))
    )
    (net (code "62") (name "PX3") (class "Default")
      (node (ref "MCU") (pin "86") (pinfunction "PK3(ADC11/PCINT19)_86") (pintype "bidirectional"))
      (node (ref "PXS3") (pin "4") (pinfunction "4_4") (pintype "passive"))
    )
    (net (code "63") (name "PX4") (class "Default")
      (node (ref "MCU") (pin "85") (pinfunction "PK4(ADC12/PCINT20)_85") (pintype "bidirectional"))
      (node (ref "PXS4") (pin "4") (pinfunction "4_4") (pintype "passive"))
    )
    (net (code "64") (name "PX5") (class "Default")
      (node (ref "MCU") (pin "84") (pinfunction "PK5(ADC13/PCINT21)_84") (pintype "bidirectional"))
      (node (ref "PXS5") (pin "4") (pinfunction "4_4") (pintype "passive"))
    )
    (net (code "65") (name "PX6") (class "Default")
      (node (ref "MCU") (pin "83") (pinfunction "PK6(ADC14/PCINT22)_83") (pintype "bidirectional"))
      (node (ref "PXS6") (pin "4") (pinfunction "4_4") (pintype "passive"))
    )
    (net (code "66") (name "PX7") (class "Default")
      (node (ref "MCU") (pin "82") (pinfunction "PK7(ADC15/PCINT23)_82") (pintype "bidirectional"))
      (node (ref "PXS7") (pin "4") (pinfunction "4_4") (pintype "passive"))
    )
    (net (code "67") (name "PX_EN") (class "Default")
      (node (ref "MCU") (pin "79") (pinfunction "PJ7_79") (pintype "bidirectional"))
      (node (ref "Q2") (pin "1") (pinfunction "G_1") (pintype "bidirectional"))
    )
    (net (code "68") (name "RS1") (class "Default")
      (node (ref "MCU") (pin "47") (pinfunction "(ICP1)PD4_47") (pintype "bidirectional"))
      (node (ref "RS1") (pin "3") (pinfunction "3_3") (pintype "passive"))
    )
    (net (code "69") (name "RS2") (class "Default")
      (node (ref "MCU") (pin "9") (pinfunction "(CLKO/ICP3/INT7)PE7_9") (pintype "bidirectional"))
      (node (ref "RS2") (pin "3") (pinfunction "3_3") (pintype "passive"))
    )
    (net (code "70") (name "RXD0") (class "Default")
      (node (ref "C13") (pin "2") (pinfunction "2_2") (pintype "passive"))
      (node (ref "MCU") (pin "2") (pinfunction "(RXD0/PCIN8)PE0_2") (pintype "bidirectional"))
      (node (ref "U3") (pin "20") (pinfunction "TXD_20") (pintype "bidirectional"))
    )
    (net (code "71") (name "RXD2") (class "Default")
      (node (ref "MCU") (pin "12") (pinfunction "PH0(RXD2)_12") (pintype "bidirectional"))
      (node (ref "U2") (pin "UTXD") (pinfunction "UTXD_UTXD") (pintype "bidirectional"))
    )
    (net (code "72") (name "SPM_PWM") (class "Default")
      (node (ref "MCU") (pin "25") (pinfunction "(OC1B/PCINT6)PB6_25") (pintype "bidirectional"))
      (node (ref "SPMOT") (pin "1") (pinfunction "1_1") (pintype "passive"))
    )
    (net (code "73") (name "TRS") (class "Default")
      (node (ref "MCU") (pin "18") (pinfunction "PH6(OC2B)_18") (pintype "bidirectional"))
      (node (ref "TRS") (pin "3") (pinfunction "3_3") (pintype "passive"))
    )
    (net (code "74") (name "TXD0") (class "Default")
      (node (ref "MCU") (pin "3") (pinfunction "(TXD0)PE1_3") (pintype "bidirectional"))
      (node (ref "U3") (pin "4") (pinfunction "RXD_4") (pintype "bidirectional"))
    )
    (net (code "75") (name "TXD2") (class "Default")
      (node (ref "MCU") (pin "13") (pinfunction "PH1(TXD2)_13") (pintype "bidirectional"))
      (node (ref "Q12") (pin "3") (pinfunction "D_3") (pintype "bidirectional"))
      (node (ref "R13") (pin "1") (pinfunction "1_1") (pintype "passive"))
    )
    (net (code "76") (name "VBAT_SEN") (class "Default")
      (node (ref "C12") (pin "2") (pinfunction "2_2") (pintype "passive"))
      (node (ref "MCU") (pin "97") (pinfunction "(ADC0)PF0_97") (pintype "bidirectional"))
      (node (ref "R11") (pin "2") (pinfunction "2_2") (pintype "passive"))
      (node (ref "R9") (pin "1") (pinfunction "1_1") (pintype "passive"))
    )
    (net (code "77") (name "VCC") (class "Default")
      (node (ref "C3") (pin "1") (pinfunction "1_1") (pintype "passive"))
      (node (ref "C7") (pin "1") (pinfunction "1_1") (pintype "passive"))
      (node (ref "GSPI") (pin "2") (pinfunction "2_2") (pintype "passive"))
      (node (ref "ISP") (pin "3") (pinfunction "VCC_3") (pintype "bidirectional"))
      (node (ref "LX") (pin "10") (pinfunction "10_10") (pintype "passive"))
      (node (ref "LX") (pin "12") (pinfunction "12_12") (pintype "passive"))
      (node (ref "LX") (pin "14") (pinfunction "14_14") (pintype "passive"))
      (node (ref "LX") (pin "16") (pinfunction "16_16") (pintype "passive"))
      (node (ref "LX") (pin "2") (pinfunction "2_2") (pintype "passive"))
      (node (ref "LX") (pin "4") (pinfunction "4_4") (pintype "passive"))
      (node (ref "LX") (pin "6") (pinfunction "6_6") (pintype "passive"))
      (node (ref "LX") (pin "8") (pinfunction "8_8") (pintype "passive"))
      (node (ref "LXS") (pin "1") (pinfunction "1_1") (pintype "passive"))
      (node (ref "MCU") (pin "10") (pinfunction "VCC_10") (pintype "power_in"))
      (node (ref "MCU") (pin "100") (pinfunction "AVCC_100") (pintype "power_in"))
      (node (ref "MCU") (pin "31") (pinfunction "VCC1_31") (pintype "power_in"))
      (node (ref "MCU") (pin "61") (pinfunction "VCC2_61") (pintype "power_in"))
      (node (ref "MCU") (pin "80") (pinfunction "VCC3_80") (pintype "power_in"))
      (node (ref "PXS0") (pin "3") (pinfunction "3_3") (pintype "passive"))
      (node (ref "PXS1") (pin "3") (pinfunction "3_3") (pintype "passive"))
      (node (ref "PXS2") (pin "3") (pinfunction "3_3") (pintype "passive"))
      (node (ref "PXS3") (pin "3") (pinfunction "3_3") (pintype "passive"))
      (node (ref "PXS4") (pin "3") (pinfunction "3_3") (pintype "passive"))
      (node (ref "PXS5") (pin "3") (pinfunction "3_3") (pintype "passive"))
      (node (ref "PXS6") (pin "3") (pinfunction "3_3") (pintype "passive"))
      (node (ref "PXS7") (pin "3") (pinfunction "3_3") (pintype "passive"))
      (node (ref "R13") (pin "2") (pinfunction "2_2") (pintype "passive"))
      (node (ref "R14") (pin "1") (pinfunction "1_1") (pintype "passive"))
      (node (ref "R15") (pin "1") (pinfunction "1_1") (pintype "passive"))
      (node (ref "R17") (pin "1") (pinfunction "1_1") (pintype "passive"))
      (node (ref "R18") (pin "1") (pinfunction "1_1") (pintype "passive"))
      (node (ref "R20") (pin "2") (pinfunction "2_2") (pintype "passive"))
      (node (ref "R21") (pin "1") (pinfunction "1_1") (pintype "passive"))
      (node (ref "R6") (pin "2") (pinfunction "2_2") (pintype "passive"))
      (node (ref "R7") (pin "2") (pinfunction "2_2") (pintype "passive"))
      (node (ref "RS1") (pin "2") (pinfunction "2_2") (pintype "passive"))
      (node (ref "RS2") (pin "2") (pinfunction "2_2") (pintype "passive"))
      (node (ref "SPKR") (pin "1") (pinfunction "1_1") (pintype "passive"))
      (node (ref "TRS") (pin "2") (pinfunction "2_2") (pintype "passive"))
      (node (ref "U3") (pin "14") (pinfunction "~{RESET}_14") (pintype "bidirectional"))
      (node (ref "U3") (pin "15") (pinfunction "VCC_15") (pintype "bidirectional"))
      (node (ref "VR1") (pin "2") (pinfunction "VOUT_2") (pintype "output"))
      (node (ref "VR1") (pin "4") (pinfunction "VOUT_4") (pintype "output"))
      (node (ref "VR2") (pin "1") (pinfunction "VIN_1") (pintype "power_in"))
      (node (ref "VR2") (pin "3") (pinfunction "CE_3") (pintype "bidirectional"))
    )
    (net (code "78") (name "VCC_1") (class "Default")
      (node (ref "ACC") (pin "1") (pinfunction "1_1") (pintype "passive"))
      (node (ref "C10") (pin "1") (pinfunction "1_1") (pintype "passive"))
      (node (ref "C4") (pin "1") (pinfunction "1_1") (pintype "passive"))
      (node (ref "Q12") (pin "1") (pinfunction "G_1") (pintype "bidirectional"))
      (node (ref "Q13") (pin "1") (pinfunction "G_1") (pintype "bidirectional"))
      (node (ref "Q14") (pin "1") (pinfunction "G_1") (pintype "bidirectional"))
      (node (ref "Q4") (pin "1") (pinfunction "G_1") (pintype "bidirectional"))
      (node (ref "Q5") (pin "1") (pinfunction "G_1") (pintype "bidirectional"))
      (node (ref "R12") (pin "2") (pinfunction "2_2") (pintype "passive"))
      (node (ref "R16") (pin "2") (pinfunction "2_2") (pintype "passive"))
      (node (ref "R19") (pin "1") (pinfunction "1_1") (pintype "passive"))
      (node (ref "R5") (pin "2") (pinfunction "2_2") (pintype "passive"))
      (node (ref "R8") (pin "2") (pinfunction "2_2") (pintype "passive"))
      (node (ref "U2") (pin "3V3") (pinfunction "VCC_3V3") (pintype "power_in"))
      (node (ref "VR2") (pin "5") (pinfunction "VOUT_5") (pintype "power_in"))
    )
    (net (code "79") (name "VIN") (class "Default")
      (node (ref "C1") (pin "1") (pinfunction "1_1") (pintype "passive"))
      (node (ref "C2") (pin "1") (pinfunction "1_1") (pintype "passive"))
      (node (ref "R9") (pin "2") (pinfunction "2_2") (pintype "passive"))
      (node (ref "SPMOT") (pin "4") (pinfunction "4_4") (pintype "passive"))
      (node (ref "VR1") (pin "3") (pinfunction "VIN_3") (pintype "input"))
    )
    (net (code "80") (name "unconnected-(J1-PadID)") (class "Default")
      (node (ref "J1") (pin "ID") (pinfunction "ID_ID") (pintype "bidirectional"))
    )
    (net (code "81") (name "unconnected-(MCU-(A8)PC0-Pad53)") (class "Default")
      (node (ref "MCU") (pin "53") (pinfunction "(A8)PC0_53") (pintype "bidirectional"))
    )
    (net (code "82") (name "unconnected-(MCU-(A9)PC1-Pad54)") (class "Default")
      (node (ref "MCU") (pin "54") (pinfunction "(A9)PC1_54") (pintype "bidirectional"))
    )
    (net (code "83") (name "unconnected-(MCU-(A10)PC2-Pad55)") (class "Default")
      (node (ref "MCU") (pin "55") (pinfunction "(A10)PC2_55") (pintype "bidirectional"))
    )
    (net (code "84") (name "unconnected-(MCU-(A11)PC3-Pad56)") (class "Default")
      (node (ref "MCU") (pin "56") (pinfunction "(A11)PC3_56") (pintype "bidirectional"))
    )
    (net (code "85") (name "unconnected-(MCU-(A12)PC4-Pad57)") (class "Default")
      (node (ref "MCU") (pin "57") (pinfunction "(A12)PC4_57") (pintype "bidirectional"))
    )
    (net (code "86") (name "unconnected-(MCU-(A13)PC5-Pad58)") (class "Default")
      (node (ref "MCU") (pin "58") (pinfunction "(A13)PC5_58") (pintype "bidirectional"))
    )
    (net (code "87") (name "unconnected-(MCU-(AD1)PA1-Pad77)") (class "Default")
      (node (ref "MCU") (pin "77") (pinfunction "(AD1)PA1_77") (pintype "bidirectional"))
    )
    (net (code "88") (name "unconnected-(MCU-(AD2)PA2-Pad76)") (class "Default")
      (node (ref "MCU") (pin "76") (pinfunction "(AD2)PA2_76") (pintype "bidirectional"))
    )
    (net (code "89") (name "unconnected-(MCU-(AD3)PA3-Pad75)") (class "Default")
      (node (ref "MCU") (pin "75") (pinfunction "(AD3)PA3_75") (pintype "bidirectional"))
    )
    (net (code "90") (name "unconnected-(MCU-(AD4)PA4-Pad74)") (class "Default")
      (node (ref "MCU") (pin "74") (pinfunction "(AD4)PA4_74") (pintype "bidirectional"))
    )
    (net (code "91") (name "unconnected-(MCU-(AD5)PA5-Pad73)") (class "Default")
      (node (ref "MCU") (pin "73") (pinfunction "(AD5)PA5_73") (pintype "bidirectional"))
    )
    (net (code "92") (name "unconnected-(MCU-(AD6)PA6-Pad72)") (class "Default")
      (node (ref "MCU") (pin "72") (pinfunction "(AD6)PA6_72") (pintype "bidirectional"))
    )
    (net (code "93") (name "unconnected-(MCU-(AD7)PA7-Pad71)") (class "Default")
      (node (ref "MCU") (pin "71") (pinfunction "(AD7)PA7_71") (pintype "bidirectional"))
    )
    (net (code "94") (name "unconnected-(MCU-(OC0A{slash}OC1C{slash}PCINT7)PB7-Pad26)") (class "Default")
      (node (ref "MCU") (pin "26") (pinfunction "(OC0A/OC1C/PCINT7)PB7_26") (pintype "bidirectional"))
    )
    (net (code "95") (name "unconnected-(MCU-(OC0B)PG5-Pad1)") (class "Default")
      (node (ref "MCU") (pin "1") (pinfunction "(OC0B)PG5_1") (pintype "bidirectional"))
    )
    (net (code "96") (name "unconnected-(MCU-(OC1A{slash}PCINT5)PB5-Pad24)") (class "Default")
      (node (ref "MCU") (pin "24") (pinfunction "(OC1A/PCINT5)PB5_24") (pintype "bidirectional"))
    )
    (net (code "97") (name "unconnected-(MCU-(OC3B{slash}INT4)PE4-Pad6)") (class "Default")
      (node (ref "MCU") (pin "6") (pinfunction "(OC3B/INT4)PE4_6") (pintype "bidirectional"))
    )
    (net (code "98") (name "unconnected-(MCU-(OC3C{slash}INT5)PE5-Pad7)") (class "Default")
      (node (ref "MCU") (pin "7") (pinfunction "(OC3C/INT5)PE5_7") (pintype "bidirectional"))
    )
    (net (code "99") (name "unconnected-(MCU-(RD)PG1-Pad52)") (class "Default")
      (node (ref "MCU") (pin "52") (pinfunction "(RD)PG1_52") (pintype "bidirectional"))
    )
    (net (code "100") (name "unconnected-(MCU-(SS{slash}PCINT0)PB0-Pad19)") (class "Default")
      (node (ref "MCU") (pin "19") (pinfunction "(SS/PCINT0)PB0_19") (pintype "bidirectional"))
    )
    (net (code "101") (name "unconnected-(MCU-(T0)PD7-Pad50)") (class "Default")
      (node (ref "MCU") (pin "50") (pinfunction "(T0)PD7_50") (pintype "bidirectional"))
    )
    (net (code "102") (name "unconnected-(MCU-(T1)PD6-Pad49)") (class "Default")
      (node (ref "MCU") (pin "49") (pinfunction "(T1)PD6_49") (pintype "bidirectional"))
    )
    (net (code "103") (name "unconnected-(MCU-(T3{slash}INT6)PE6-Pad8)") (class "Default")
      (node (ref "MCU") (pin "8") (pinfunction "(T3/INT6)PE6_8") (pintype "bidirectional"))
    )
    (net (code "104") (name "unconnected-(MCU-(TOSC1)PG4-Pad29)") (class "Default")
      (node (ref "MCU") (pin "29") (pinfunction "(TOSC1)PG4_29") (pintype "bidirectional"))
    )
    (net (code "105") (name "unconnected-(MCU-(TOSC2)PG3-Pad28)") (class "Default")
      (node (ref "MCU") (pin "28") (pinfunction "(TOSC2)PG3_28") (pintype "bidirectional"))
    )
    (net (code "106") (name "unconnected-(MCU-(WR)PG0-Pad51)") (class "Default")
      (node (ref "MCU") (pin "51") (pinfunction "(WR)PG0_51") (pintype "bidirectional"))
    )
    (net (code "107") (name "unconnected-(MCU-(XCK1)PD5-Pad48)") (class "Default")
      (node (ref "MCU") (pin "48") (pinfunction "(XCK1)PD5_48") (pintype "bidirectional"))
    )
    (net (code "108") (name "unconnected-(MCU-PH2(XCK2)-Pad14)") (class "Default")
      (node (ref "MCU") (pin "14") (pinfunction "PH2(XCK2)_14") (pintype "bidirectional"))
    )
    (net (code "109") (name "unconnected-(MCU-PH3(OC4A)-Pad15)") (class "Default")
      (node (ref "MCU") (pin "15") (pinfunction "PH3(OC4A)_15") (pintype "bidirectional"))
    )
    (net (code "110") (name "unconnected-(MCU-PH4(OC4B)-Pad16)") (class "Default")
      (node (ref "MCU") (pin "16") (pinfunction "PH4(OC4B)_16") (pintype "bidirectional"))
    )
    (net (code "111") (name "unconnected-(MCU-PH5(OC4C)-Pad17)") (class "Default")
      (node (ref "MCU") (pin "17") (pinfunction "PH5(OC4C)_17") (pintype "bidirectional"))
    )
    (net (code "112") (name "unconnected-(MCU-PH7(T4)-Pad27)") (class "Default")
      (node (ref "MCU") (pin "27") (pinfunction "PH7(T4)_27") (pintype "bidirectional"))
    )
    (net (code "113") (name "unconnected-(MCU-PJ0(RXD3{slash}PCINT9)-Pad63)") (class "Default")
      (node (ref "MCU") (pin "63") (pinfunction "PJ0(RXD3/PCINT9)_63") (pintype "bidirectional"))
    )
    (net (code "114") (name "unconnected-(MCU-PJ1(TXD3{slash}PCINT10)-Pad64)") (class "Default")
      (node (ref "MCU") (pin "64") (pinfunction "PJ1(TXD3/PCINT10)_64") (pintype "bidirectional"))
    )
    (net (code "115") (name "unconnected-(MCU-PJ2(XCK3{slash}PCINT11)-Pad65)") (class "Default")
      (node (ref "MCU") (pin "65") (pinfunction "PJ2(XCK3/PCINT11)_65") (pintype "bidirectional"))
    )
    (net (code "116") (name "unconnected-(MCU-PJ3(PCINT12)-Pad66)") (class "Default")
      (node (ref "MCU") (pin "66") (pinfunction "PJ3(PCINT12)_66") (pintype "bidirectional"))
    )
    (net (code "117") (name "unconnected-(MCU-PJ4(PCINT13)-Pad67)") (class "Default")
      (node (ref "MCU") (pin "67") (pinfunction "PJ4(PCINT13)_67") (pintype "bidirectional"))
    )
    (net (code "118") (name "unconnected-(MCU-PJ5(PCINT14)-Pad68)") (class "Default")
      (node (ref "MCU") (pin "68") (pinfunction "PJ5(PCINT14)_68") (pintype "bidirectional"))
    )
    (net (code "119") (name "unconnected-(MCU-PJ6(PCINT15)-Pad69)") (class "Default")
      (node (ref "MCU") (pin "69") (pinfunction "PJ6(PCINT15)_69") (pintype "bidirectional"))
    )
    (net (code "120") (name "unconnected-(MCU-PL2(T5)-Pad37)") (class "Default")
      (node (ref "MCU") (pin "37") (pinfunction "PL2(T5)_37") (pintype "bidirectional"))
    )
    (net (code "121") (name "unconnected-(MCU-PL6-Pad41)") (class "Default")
      (node (ref "MCU") (pin "41") (pinfunction "PL6_41") (pintype "bidirectional"))
    )
    (net (code "122") (name "unconnected-(MCU-PL7-Pad42)") (class "Default")
      (node (ref "MCU") (pin "42") (pinfunction "PL7_42") (pintype "bidirectional"))
    )
    (net (code "123") (name "unconnected-(U2-PadIO0)") (class "Default")
      (node (ref "U2") (pin "IO0") (pinfunction "IO0_IO0") (pintype "bidirectional"))
    )
    (net (code "124") (name "unconnected-(U2-PadIO2)") (class "Default")
      (node (ref "U2") (pin "IO2") (pinfunction "IO2_IO2") (pintype "bidirectional"))
    )
    (net (code "125") (name "unconnected-(U2-PadIO4)") (class "Default")
      (node (ref "U2") (pin "IO4") (pinfunction "IO4_IO4") (pintype "bidirectional"))
    )
    (net (code "126") (name "unconnected-(U2-PadIO5)") (class "Default")
      (node (ref "U2") (pin "IO5") (pinfunction "IO5_IO5") (pintype "bidirectional"))
    )
    (net (code "127") (name "unconnected-(U2-PadIO12)") (class "Default")
      (node (ref "U2") (pin "IO12") (pinfunction "IO12_IO12") (pintype "bidirectional"))
    )
    (net (code "128") (name "unconnected-(U2-PadIO13)") (class "Default")
      (node (ref "U2") (pin "IO13") (pinfunction "IO13_IO13") (pintype "bidirectional"))
    )
    (net (code "129") (name "unconnected-(U2-PadIO14)") (class "Default")
      (node (ref "U2") (pin "IO14") (pinfunction "IO14_IO14") (pintype "bidirectional"))
    )
    (net (code "130") (name "unconnected-(U2-PadIO15)") (class "Default")
      (node (ref "U2") (pin "IO15") (pinfunction "IO15_IO15") (pintype "bidirectional"))
    )
    (net (code "131") (name "unconnected-(U2-PadIO16)") (class "Default")
      (node (ref "U2") (pin "IO16") (pinfunction "IO16_IO16") (pintype "bidirectional"))
    )
    (net (code "132") (name "unconnected-(U2-PadTOUT)") (class "Default")
      (node (ref "U2") (pin "TOUT") (pinfunction "TOUT_TOUT") (pintype "bidirectional"))
    )
    (net (code "133") (name "unconnected-(U3-CBUS2-Pad10)") (class "Default")
      (node (ref "U3") (pin "10") (pinfunction "CBUS2_10") (pintype "bidirectional"))
    )
    (net (code "134") (name "unconnected-(U3-~{CTS}-Pad9)") (class "Default")
      (node (ref "U3") (pin "9") (pinfunction "~{CTS}_9") (pintype "bidirectional"))
    )
    (net (code "135") (name "unconnected-(U3-~{DCD}-Pad8)") (class "Default")
      (node (ref "U3") (pin "8") (pinfunction "~{DCD}_8") (pintype "bidirectional"))
    )
    (net (code "136") (name "unconnected-(U3-~{DSR}-Pad7)") (class "Default")
      (node (ref "U3") (pin "7") (pinfunction "~{DSR}_7") (pintype "bidirectional"))
    )
    (net (code "137") (name "unconnected-(U3-~{RI}-Pad5)") (class "Default")
      (node (ref "U3") (pin "5") (pinfunction "~{RI}_5") (pintype "bidirectional"))
    )
    (net (code "138") (name "unconnected-(U3-~{RTS}-Pad2)") (class "Default")
      (node (ref "U3") (pin "2") (pinfunction "~{RTS}_2") (pintype "bidirectional"))
    )
  )
)
